# CajitaAbierta_stick.net
KiCad netlist of a schematic drawn in EAGLE
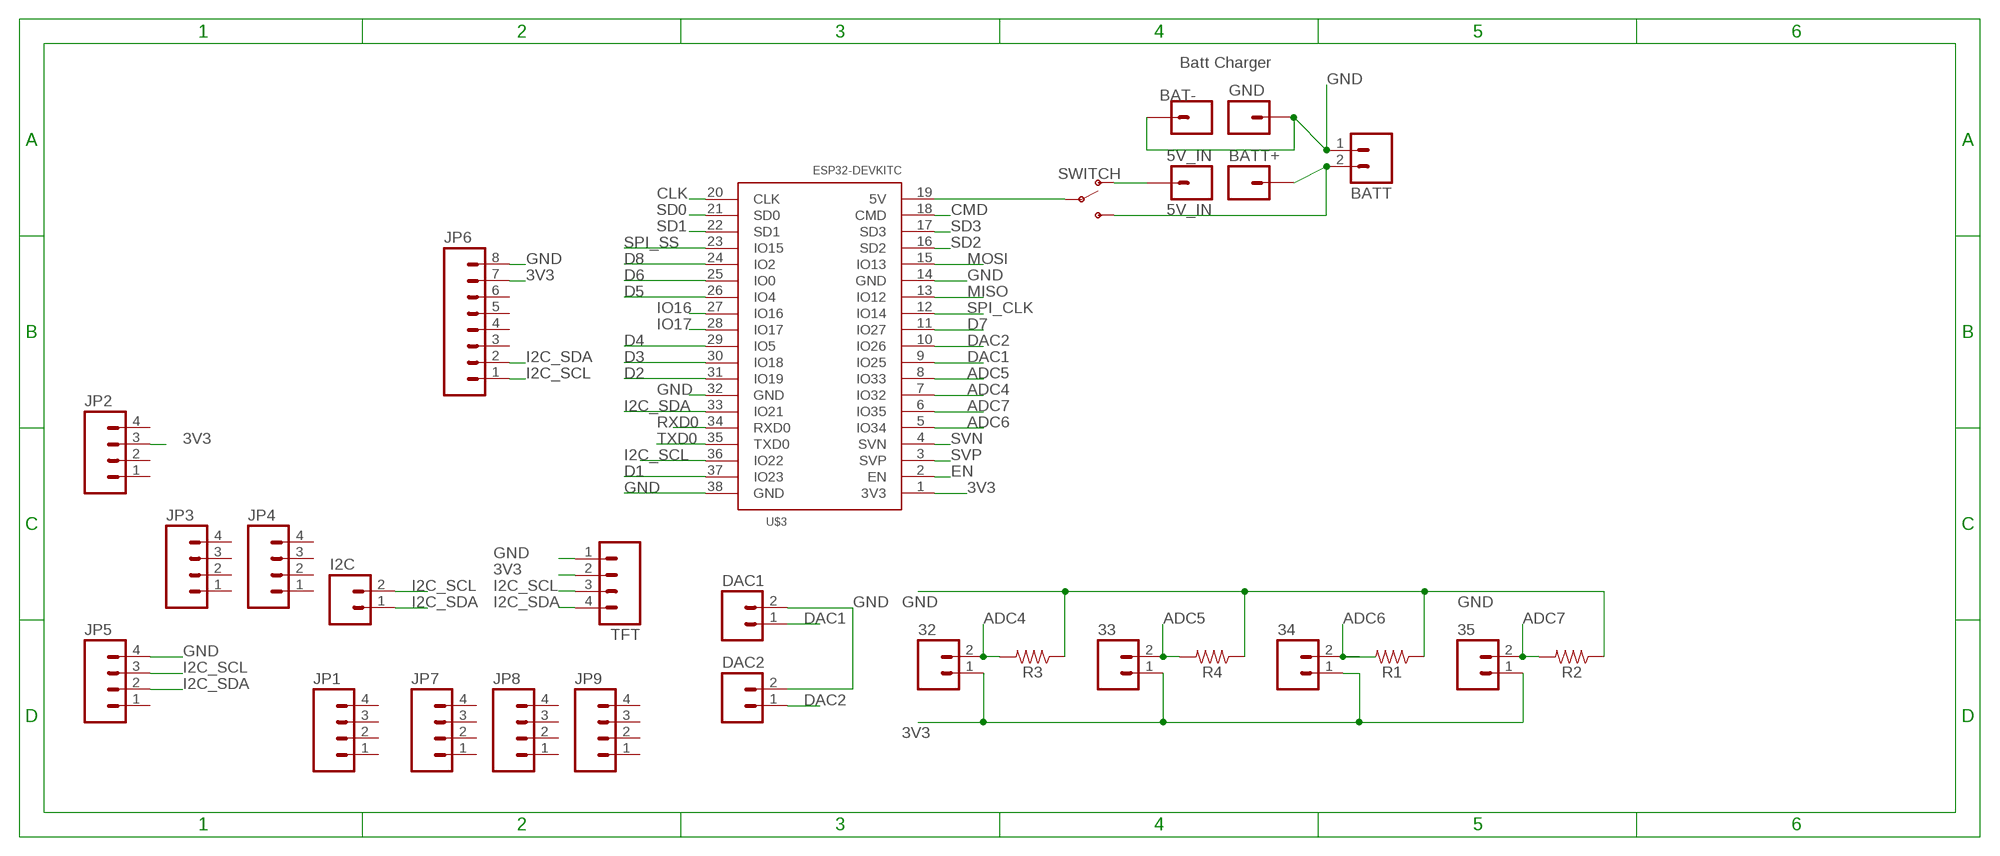
[diagram p0: schematic, sheet 1]

(export (version "E")
  (design (tool "Eeschema 10.0.6"))
  (components
    (comp (ref "5V_IN")
      (value "5V_IN")
      (footprint "eagle-import:1X01")
      (libsource (lib "eagle-import") (part "M01PTH"))
    )
    (comp (ref "32")
      (value "M02PTH")
      (footprint "eagle-import:1X02")
      (libsource (lib "eagle-import") (part "SparkFun-Connectors_6242394_M02PTH"))
    )
    (comp (ref "33")
      (value "M02PTH")
      (footprint "eagle-import:1X02")
      (libsource (lib "eagle-import") (part "SparkFun-Connectors_6242394_M02PTH"))
    )
    (comp (ref "34")
      (value "M02PTH")
      (footprint "eagle-import:1X02")
      (libsource (lib "eagle-import") (part "SparkFun-Connectors_6242394_M02PTH"))
    )
    (comp (ref "35")
      (value "M02PTH")
      (footprint "eagle-import:1X02")
      (libsource (lib "eagle-import") (part "SparkFun-Connectors_6242394_M02PTH"))
    )
    (comp (ref "BAT-")
      (value "M01PTH")
      (footprint "eagle-import:1X01")
      (libsource (lib "eagle-import") (part "M01PTH"))
    )
    (comp (ref "BATT")
      (value "M02LOCK_LONGPADS")
      (footprint "eagle-import:1X02_LOCK_LONGPADS")
      (libsource (lib "eagle-import") (part "M02LOCK_LONGPADS"))
    )
    (comp (ref "BATT+")
      (value "M01PTH")
      (footprint "eagle-import:1X01")
      (libsource (lib "eagle-import") (part "M01PTH"))
    )
    (comp (ref "DAC1")
      (value "M02PTH")
      (footprint "eagle-import:1X02")
      (libsource (lib "eagle-import") (part "SparkFun-Connectors_6242394_M02PTH"))
    )
    (comp (ref "DAC2")
      (value "M02PTH")
      (footprint "eagle-import:1X02")
      (libsource (lib "eagle-import") (part "SparkFun-Connectors_6242394_M02PTH"))
    )
    (comp (ref "GND")
      (value "Batt Charger")
      (footprint "eagle-import:1X01")
      (libsource (lib "eagle-import") (part "M01PTH"))
    )
    (comp (ref "I2C")
      (value "M02PTH")
      (footprint "eagle-import:1X02")
      (libsource (lib "eagle-import") (part "SparkFun-Connectors_6242394_M02PTH"))
    )
    (comp (ref "JP1")
      (value "M04NO_SILK_ALL_ROUND")
      (footprint "eagle-import:1X04_NO_SILK_ALL_ROUND")
      (libsource (lib "eagle-import") (part "M04NO_SILK_ALL_ROUND"))
    )
    (comp (ref "JP2")
      (value "M04NO_SILK_ALL_ROUND")
      (footprint "eagle-import:1X04_NO_SILK_ALL_ROUND")
      (libsource (lib "eagle-import") (part "M04NO_SILK_ALL_ROUND"))
    )
    (comp (ref "JP3")
      (value "M04NO_SILK_ALL_ROUND")
      (footprint "eagle-import:1X04_NO_SILK_ALL_ROUND")
      (libsource (lib "eagle-import") (part "M04NO_SILK_ALL_ROUND"))
    )
    (comp (ref "JP4")
      (value "M04NO_SILK_ALL_ROUND")
      (footprint "eagle-import:1X04_NO_SILK_ALL_ROUND")
      (libsource (lib "eagle-import") (part "M04NO_SILK_ALL_ROUND"))
    )
    (comp (ref "JP5")
      (value "M04NO_SILK_ALL_ROUND")
      (footprint "eagle-import:1X04_NO_SILK_ALL_ROUND")
      (libsource (lib "eagle-import") (part "M04NO_SILK_ALL_ROUND"))
    )
    (comp (ref "JP6")
      (value "M08")
      (footprint "eagle-import:1X08_ROUND")
      (libsource (lib "eagle-import") (part "M08"))
    )
    (comp (ref "JP7")
      (value "M04NO_SILK_ALL_ROUND")
      (footprint "eagle-import:1X04_NO_SILK_ALL_ROUND")
      (libsource (lib "eagle-import") (part "M04NO_SILK_ALL_ROUND"))
    )
    (comp (ref "JP8")
      (value "M04NO_SILK_ALL_ROUND")
      (footprint "eagle-import:1X04_NO_SILK_ALL_ROUND")
      (libsource (lib "eagle-import") (part "M04NO_SILK_ALL_ROUND"))
    )
    (comp (ref "JP9")
      (value "M04NO_SILK_ALL_ROUND")
      (footprint "eagle-import:1X04_NO_SILK_ALL_ROUND")
      (libsource (lib "eagle-import") (part "M04NO_SILK_ALL_ROUND"))
    )
    (comp (ref "R1")
      (value "RESISTOR1206")
      (footprint "eagle-import:1206")
      (libsource (lib "eagle-import") (part "RESISTOR1206"))
    )
    (comp (ref "R2")
      (value "RESISTOR1206")
      (footprint "eagle-import:1206")
      (libsource (lib "eagle-import") (part "RESISTOR1206"))
    )
    (comp (ref "R3")
      (value "RESISTOR1206")
      (footprint "eagle-import:1206")
      (libsource (lib "eagle-import") (part "RESISTOR1206"))
    )
    (comp (ref "R4")
      (value "RESISTOR1206")
      (footprint "eagle-import:1206")
      (libsource (lib "eagle-import") (part "RESISTOR1206"))
    )
    (comp (ref "SWITCH")
      (value "SWITCH-SPDT-SMD-RIGHT-ANGLE")
      (footprint "eagle-import:SWITCH_SPST_SMD_A")
      (libsource (lib "eagle-import") (part "SWITCH-SPDT-SMD-RIGHT-ANGLE"))
    )
    (comp (ref "TFT")
      (value "M04PTH")
      (footprint "eagle-import:1X04")
      (libsource (lib "eagle-import") (part "M04PTH"))
    )
    (comp (ref "U$3")
      (value "ESP32DEVKITC")
      (footprint "eagle-import:ESP32-DEVKITC")
      (libsource (lib "eagle-import") (part "ESP32DEVKITC"))
    )
  )
  (nets
    (net (code "1") (name "/3V3") (class "Default")
      (node (ref "32") (pin "1") (pinfunction "1_1") (pintype "passive"))
      (node (ref "33") (pin "1") (pinfunction "1_1") (pintype "passive"))
      (node (ref "34") (pin "1") (pinfunction "1_1") (pintype "passive"))
      (node (ref "35") (pin "1") (pinfunction "1_1") (pintype "passive"))
      (node (ref "JP2") (pin "3") (pinfunction "3_3") (pintype "passive"))
      (node (ref "JP6") (pin "7") (pinfunction "7_7") (pintype "passive"))
      (node (ref "TFT") (pin "2") (pinfunction "2_2") (pintype "passive"))
      (node (ref "U$3") (pin "1") (pinfunction "3V3_1") (pintype "bidirectional"))
    )
    (net (code "2") (name "/ADC4") (class "Default")
      (node (ref "32") (pin "2") (pinfunction "2_2") (pintype "passive"))
      (node (ref "R3") (pin "2") (pinfunction "2_2") (pintype "passive"))
      (node (ref "U$3") (pin "7") (pinfunction "IO32_7") (pintype "bidirectional"))
    )
    (net (code "3") (name "/ADC5") (class "Default")
      (node (ref "33") (pin "2") (pinfunction "2_2") (pintype "passive"))
      (node (ref "R4") (pin "2") (pinfunction "2_2") (pintype "passive"))
      (node (ref "U$3") (pin "8") (pinfunction "IO33_8") (pintype "bidirectional"))
    )
    (net (code "4") (name "/ADC6") (class "Default")
      (node (ref "34") (pin "2") (pinfunction "2_2") (pintype "passive"))
      (node (ref "R1") (pin "2") (pinfunction "2_2") (pintype "passive"))
      (node (ref "U$3") (pin "5") (pinfunction "IO34_5") (pintype "bidirectional"))
    )
    (net (code "5") (name "/ADC7") (class "Default")
      (node (ref "35") (pin "2") (pinfunction "2_2") (pintype "passive"))
      (node (ref "R2") (pin "2") (pinfunction "2_2") (pintype "passive"))
      (node (ref "U$3") (pin "6") (pinfunction "IO35_6") (pintype "bidirectional"))
    )
    (net (code "6") (name "/CLK") (class "Default")
      (node (ref "U$3") (pin "20") (pinfunction "CLK_20") (pintype "bidirectional"))
    )
    (net (code "7") (name "/CMD") (class "Default")
      (node (ref "U$3") (pin "18") (pinfunction "CMD_18") (pintype "bidirectional"))
    )
    (net (code "8") (name "/D1") (class "Default")
      (node (ref "U$3") (pin "37") (pinfunction "IO23_37") (pintype "bidirectional"))
    )
    (net (code "9") (name "/D2") (class "Default")
      (node (ref "U$3") (pin "31") (pinfunction "IO19_31") (pintype "bidirectional"))
    )
    (net (code "10") (name "/D3") (class "Default")
      (node (ref "U$3") (pin "30") (pinfunction "IO18_30") (pintype "bidirectional"))
    )
    (net (code "11") (name "/D4") (class "Default")
      (node (ref "U$3") (pin "29") (pinfunction "IO5_29") (pintype "bidirectional"))
    )
    (net (code "12") (name "/D5") (class "Default")
      (node (ref "U$3") (pin "26") (pinfunction "IO4_26") (pintype "bidirectional"))
    )
    (net (code "13") (name "/D6") (class "Default")
      (node (ref "U$3") (pin "25") (pinfunction "IO0_25") (pintype "bidirectional"))
    )
    (net (code "14") (name "/D7") (class "Default")
      (node (ref "U$3") (pin "11") (pinfunction "IO27_11") (pintype "bidirectional"))
    )
    (net (code "15") (name "/D8") (class "Default")
      (node (ref "U$3") (pin "24") (pinfunction "IO2_24") (pintype "bidirectional"))
    )
    (net (code "16") (name "/DAC1") (class "Default")
      (node (ref "DAC1") (pin "1") (pinfunction "1_1") (pintype "passive"))
      (node (ref "U$3") (pin "9") (pinfunction "IO25_9") (pintype "bidirectional"))
    )
    (net (code "17") (name "/DAC2") (class "Default")
      (node (ref "DAC2") (pin "1") (pinfunction "1_1") (pintype "passive"))
      (node (ref "U$3") (pin "10") (pinfunction "IO26_10") (pintype "bidirectional"))
    )
    (net (code "18") (name "/EN") (class "Default")
      (node (ref "U$3") (pin "2") (pinfunction "EN_2") (pintype "bidirectional"))
    )
    (net (code "19") (name "/GND") (class "Default")
      (node (ref "BAT-") (pin "1") (pinfunction "1_1") (pintype "passive"))
      (node (ref "BATT") (pin "1") (pinfunction "1_1") (pintype "passive"))
      (node (ref "DAC1") (pin "2") (pinfunction "2_2") (pintype "passive"))
      (node (ref "DAC2") (pin "2") (pinfunction "2_2") (pintype "passive"))
      (node (ref "GND") (pin "1") (pinfunction "1_1") (pintype "passive"))
      (node (ref "JP5") (pin "4") (pinfunction "4_4") (pintype "passive"))
      (node (ref "JP6") (pin "8") (pinfunction "8_8") (pintype "passive"))
      (node (ref "R1") (pin "1") (pinfunction "1_1") (pintype "passive"))
      (node (ref "R2") (pin "1") (pinfunction "1_1") (pintype "passive"))
      (node (ref "R3") (pin "1") (pinfunction "1_1") (pintype "passive"))
      (node (ref "R4") (pin "1") (pinfunction "1_1") (pintype "passive"))
      (node (ref "TFT") (pin "1") (pinfunction "1_1") (pintype "passive"))
      (node (ref "U$3") (pin "14") (pinfunction "GND_14") (pintype "bidirectional"))
      (node (ref "U$3") (pin "32") (pinfunction "GND_32") (pintype "bidirectional"))
      (node (ref "U$3") (pin "38") (pinfunction "GND_38") (pintype "bidirectional"))
    )
    (net (code "20") (name "/I2C_SCL") (class "Default")
      (node (ref "I2C") (pin "2") (pinfunction "2_2") (pintype "passive"))
      (node (ref "JP5") (pin "3") (pinfunction "3_3") (pintype "passive"))
      (node (ref "JP6") (pin "1") (pinfunction "1_1") (pintype "passive"))
      (node (ref "TFT") (pin "3") (pinfunction "3_3") (pintype "passive"))
      (node (ref "U$3") (pin "36") (pinfunction "IO22_36") (pintype "bidirectional"))
    )
    (net (code "21") (name "/I2C_SDA") (class "Default")
      (node (ref "I2C") (pin "1") (pinfunction "1_1") (pintype "passive"))
      (node (ref "JP5") (pin "2") (pinfunction "2_2") (pintype "passive"))
      (node (ref "JP6") (pin "2") (pinfunction "2_2") (pintype "passive"))
      (node (ref "TFT") (pin "4") (pinfunction "4_4") (pintype "passive"))
      (node (ref "U$3") (pin "33") (pinfunction "IO21_33") (pintype "bidirectional"))
    )
    (net (code "22") (name "/IO16") (class "Default")
      (node (ref "U$3") (pin "27") (pinfunction "IO16_27") (pintype "bidirectional"))
    )
    (net (code "23") (name "/IO17") (class "Default")
      (node (ref "U$3") (pin "28") (pinfunction "IO17_28") (pintype "bidirectional"))
    )
    (net (code "24") (name "/MISO") (class "Default")
      (node (ref "U$3") (pin "13") (pinfunction "IO12_13") (pintype "bidirectional"))
    )
    (net (code "25") (name "/MOSI") (class "Default")
      (node (ref "U$3") (pin "15") (pinfunction "IO13_15") (pintype "bidirectional"))
    )
    (net (code "26") (name "/RXD0") (class "Default")
      (node (ref "U$3") (pin "34") (pinfunction "RXD0_34") (pintype "bidirectional"))
    )
    (net (code "27") (name "/SD0") (class "Default")
      (node (ref "U$3") (pin "21") (pinfunction "SD0_21") (pintype "bidirectional"))
    )
    (net (code "28") (name "/SD1") (class "Default")
      (node (ref "U$3") (pin "22") (pinfunction "SD1_22") (pintype "bidirectional"))
    )
    (net (code "29") (name "/SD2") (class "Default")
      (node (ref "U$3") (pin "16") (pinfunction "SD2_16") (pintype "bidirectional"))
    )
    (net (code "30") (name "/SD3") (class "Default")
      (node (ref "U$3") (pin "17") (pinfunction "SD3_17") (pintype "bidirectional"))
    )
    (net (code "31") (name "/SPI_CLK") (class "Default")
      (node (ref "U$3") (pin "12") (pinfunction "IO14_12") (pintype "bidirectional"))
    )
    (net (code "32") (name "/SPI_SS") (class "Default")
      (node (ref "U$3") (pin "23") (pinfunction "IO15_23") (pintype "bidirectional"))
    )
    (net (code "33") (name "/SVN") (class "Default")
      (node (ref "U$3") (pin "4") (pinfunction "SVN_4") (pintype "bidirectional"))
    )
    (net (code "34") (name "/SVP") (class "Default")
      (node (ref "U$3") (pin "3") (pinfunction "SVP_3") (pintype "bidirectional"))
    )
    (net (code "35") (name "/TXD0") (class "Default")
      (node (ref "U$3") (pin "35") (pinfunction "TXD0_35") (pintype "bidirectional"))
    )
    (net (code "36") (name "Net-(SWITCH-O)") (class "Default")
      (node (ref "5V_IN") (pin "1") (pinfunction "1_1") (pintype "passive"))
      (node (ref "SWITCH") (pin "1") (pinfunction "O_1") (pintype "passive"))
    )
    (net (code "37") (name "Net-(SWITCH-P)") (class "Default")
      (node (ref "SWITCH") (pin "2") (pinfunction "P_2") (pintype "passive"))
      (node (ref "U$3") (pin "19") (pinfunction "5V_19") (pintype "bidirectional"))
    )
    (net (code "38") (name "Net-(SWITCH-S)") (class "Default")
      (node (ref "BATT") (pin "2") (pinfunction "2_2") (pintype "passive"))
      (node (ref "BATT+") (pin "1") (pinfunction "1_1") (pintype "passive"))
      (node (ref "SWITCH") (pin "3") (pinfunction "S_3") (pintype "passive"))
    )
    (net (code "39") (name "unconnected-(JP1-Pad1)") (class "Default")
      (node (ref "JP1") (pin "1") (pinfunction "1_1") (pintype "passive"))
    )
    (net (code "40") (name "unconnected-(JP1-Pad2)") (class "Default")
      (node (ref "JP1") (pin "2") (pinfunction "2_2") (pintype "passive"))
    )
    (net (code "41") (name "unconnected-(JP1-Pad3)") (class "Default")
      (node (ref "JP1") (pin "3") (pinfunction "3_3") (pintype "passive"))
    )
    (net (code "42") (name "unconnected-(JP1-Pad4)") (class "Default")
      (node (ref "JP1") (pin "4") (pinfunction "4_4") (pintype "passive"))
    )
    (net (code "43") (name "unconnected-(JP2-Pad1)") (class "Default")
      (node (ref "JP2") (pin "1") (pinfunction "1_1") (pintype "passive"))
    )
    (net (code "44") (name "unconnected-(JP2-Pad2)") (class "Default")
      (node (ref "JP2") (pin "2") (pinfunction "2_2") (pintype "passive"))
    )
    (net (code "45") (name "unconnected-(JP2-Pad4)") (class "Default")
      (node (ref "JP2") (pin "4") (pinfunction "4_4") (pintype "passive"))
    )
    (net (code "46") (name "unconnected-(JP3-Pad1)") (class "Default")
      (node (ref "JP3") (pin "1") (pinfunction "1_1") (pintype "passive"))
    )
    (net (code "47") (name "unconnected-(JP3-Pad2)") (class "Default")
      (node (ref "JP3") (pin "2") (pinfunction "2_2") (pintype "passive"))
    )
    (net (code "48") (name "unconnected-(JP3-Pad3)") (class "Default")
      (node (ref "JP3") (pin "3") (pinfunction "3_3") (pintype "passive"))
    )
    (net (code "49") (name "unconnected-(JP3-Pad4)") (class "Default")
      (node (ref "JP3") (pin "4") (pinfunction "4_4") (pintype "passive"))
    )
    (net (code "50") (name "unconnected-(JP4-Pad1)") (class "Default")
      (node (ref "JP4") (pin "1") (pinfunction "1_1") (pintype "passive"))
    )
    (net (code "51") (name "unconnected-(JP4-Pad2)") (class "Default")
      (node (ref "JP4") (pin "2") (pinfunction "2_2") (pintype "passive"))
    )
    (net (code "52") (name "unconnected-(JP4-Pad3)") (class "Default")
      (node (ref "JP4") (pin "3") (pinfunction "3_3") (pintype "passive"))
    )
    (net (code "53") (name "unconnected-(JP4-Pad4)") (class "Default")
      (node (ref "JP4") (pin "4") (pinfunction "4_4") (pintype "passive"))
    )
    (net (code "54") (name "unconnected-(JP5-Pad1)") (class "Default")
      (node (ref "JP5") (pin "1") (pinfunction "1_1") (pintype "passive"))
    )
    (net (code "55") (name "unconnected-(JP6-Pad3)") (class "Default")
      (node (ref "JP6") (pin "3") (pinfunction "3_3") (pintype "passive"))
    )
    (net (code "56") (name "unconnected-(JP6-Pad4)") (class "Default")
      (node (ref "JP6") (pin "4") (pinfunction "4_4") (pintype "passive"))
    )
    (net (code "57") (name "unconnected-(JP6-Pad5)") (class "Default")
      (node (ref "JP6") (pin "5") (pinfunction "5_5") (pintype "passive"))
    )
    (net (code "58") (name "unconnected-(JP6-Pad6)") (class "Default")
      (node (ref "JP6") (pin "6") (pinfunction "6_6") (pintype "passive"))
    )
    (net (code "59") (name "unconnected-(JP7-Pad1)") (class "Default")
      (node (ref "JP7") (pin "1") (pinfunction "1_1") (pintype "passive"))
    )
    (net (code "60") (name "unconnected-(JP7-Pad2)") (class "Default")
      (node (ref "JP7") (pin "2") (pinfunction "2_2") (pintype "passive"))
    )
    (net (code "61") (name "unconnected-(JP7-Pad3)") (class "Default")
      (node (ref "JP7") (pin "3") (pinfunction "3_3") (pintype "passive"))
    )
    (net (code "62") (name "unconnected-(JP7-Pad4)") (class "Default")
      (node (ref "JP7") (pin "4") (pinfunction "4_4") (pintype "passive"))
    )
    (net (code "63") (name "unconnected-(JP8-Pad1)") (class "Default")
      (node (ref "JP8") (pin "1") (pinfunction "1_1") (pintype "passive"))
    )
    (net (code "64") (name "unconnected-(JP8-Pad2)") (class "Default")
      (node (ref "JP8") (pin "2") (pinfunction "2_2") (pintype "passive"))
    )
    (net (code "65") (name "unconnected-(JP8-Pad3)") (class "Default")
      (node (ref "JP8") (pin "3") (pinfunction "3_3") (pintype "passive"))
    )
    (net (code "66") (name "unconnected-(JP8-Pad4)") (class "Default")
      (node (ref "JP8") (pin "4") (pinfunction "4_4") (pintype "passive"))
    )
    (net (code "67") (name "unconnected-(JP9-Pad1)") (class "Default")
      (node (ref "JP9") (pin "1") (pinfunction "1_1") (pintype "passive"))
    )
    (net (code "68") (name "unconnected-(JP9-Pad2)") (class "Default")
      (node (ref "JP9") (pin "2") (pinfunction "2_2") (pintype "passive"))
    )
    (net (code "69") (name "unconnected-(JP9-Pad3)") (class "Default")
      (node (ref "JP9") (pin "3") (pinfunction "3_3") (pintype "passive"))
    )
    (net (code "70") (name "unconnected-(JP9-Pad4)") (class "Default")
      (node (ref "JP9") (pin "4") (pinfunction "4_4") (pintype "passive"))
    )
  )
)
